# SSFocuser-B-TMC2208-O.net
KiCad netlist of a schematic drawn in Altium Designer
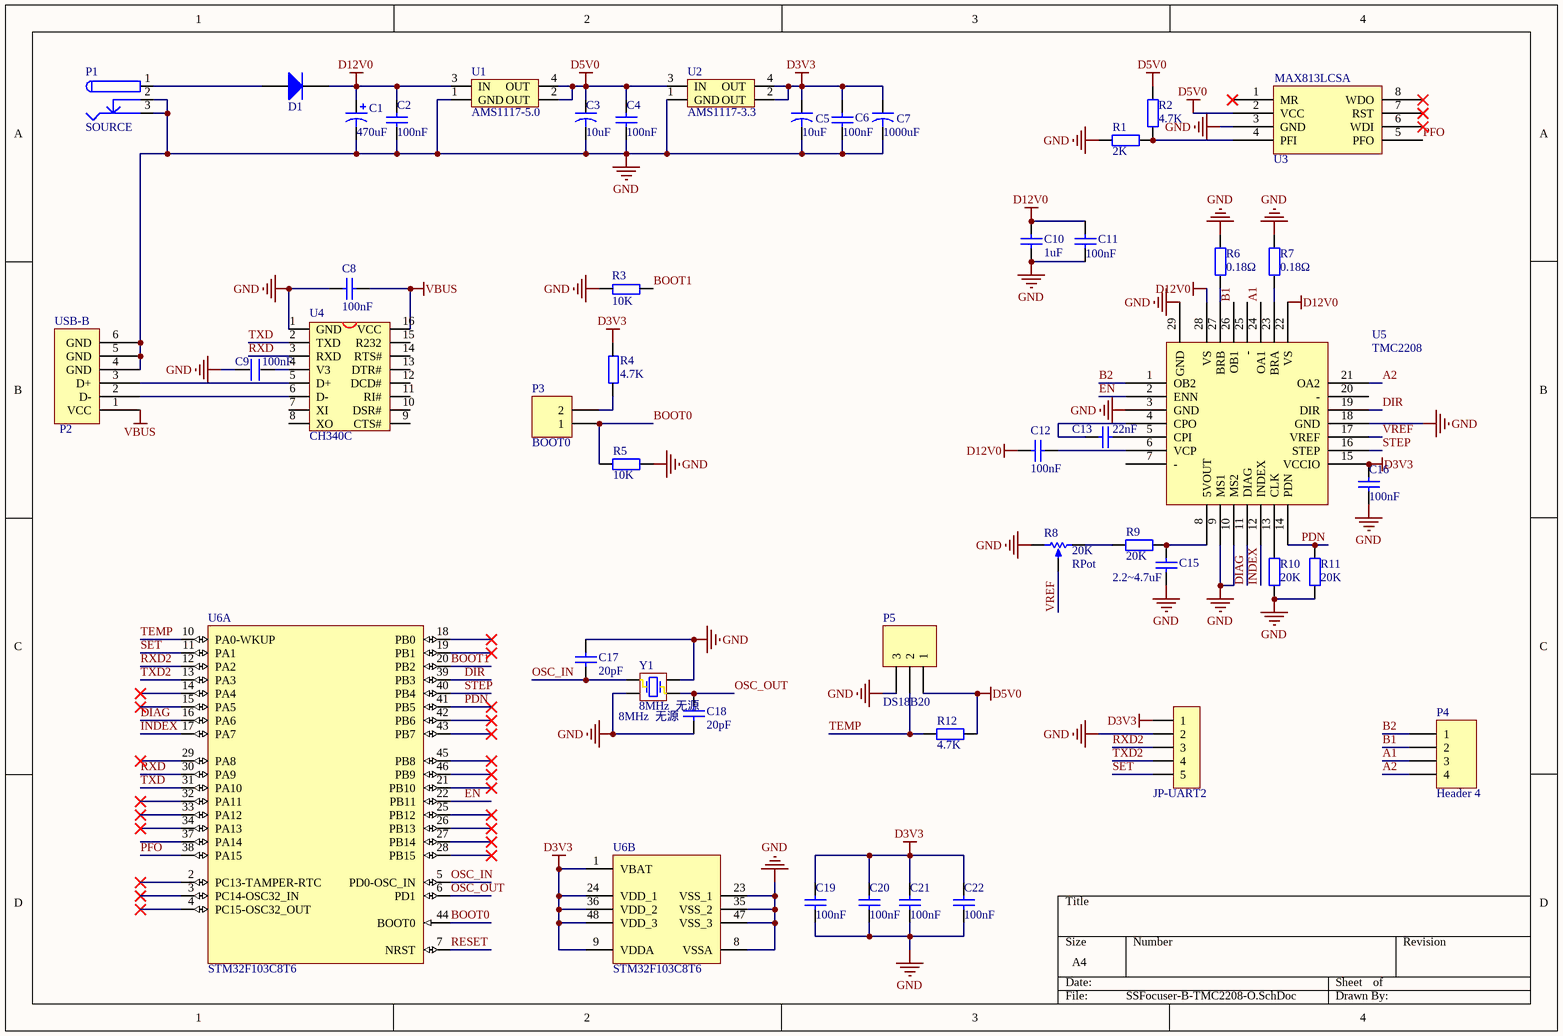
[diagram p0: SSFocuser-B-TMC2208-O.SchDoc]

(export (version "E")
  (design (tool "Eeschema 10.0.6"))
  (components
    (comp (ref "C1")
      (value "470uF")
      (footprint "16V/470U(CD10X10D5)")
      (description "470UF      16V      CD10X10D5")
      (libsource (lib "平台原理图symbol图库V1.0") (part "C470UF016S"))
    )
    (comp (ref "C2")
      (value "100nF")
      (footprint "0603C")
      (description "Capacitor")
      (fields (field (name "PUBLISHER") "Altium Limited"))
      (libsource (lib "Crazy_PCB") (part "Cap"))
    )
    (comp (ref "C3")
      (value "10uF")
      (footprint "3216")
      (fields (field (name "VAULE") "10uF"))
      (libsource (lib "Crazy_PCB") (part "CAP2"))
    )
    (comp (ref "C4")
      (value "100nF")
      (footprint "0603C")
      (description "Capacitor")
      (fields (field (name "PUBLISHER") "Altium Limited"))
      (libsource (lib "Crazy_PCB") (part "Cap"))
    )
    (comp (ref "C5")
      (value "10uF")
      (footprint "3216")
      (fields (field (name "VAULE") "10uF"))
      (libsource (lib "Crazy_PCB") (part "CAP2"))
    )
    (comp (ref "C6")
      (value "100nF")
      (footprint "0603C")
      (description "Capacitor")
      (fields (field (name "PUBLISHER") "Altium Limited"))
      (libsource (lib "Crazy_PCB") (part "Cap"))
    )
    (comp (ref "C7")
      (value "1000uF")
      (footprint "16V/470U(CD10X10D5)")
      (fields (field (name "VAULE") "1000uF"))
      (libsource (lib "Crazy_PCB") (part "CAP2"))
    )
    (comp (ref "C8")
      (value "100nF")
      (footprint "0603C")
      (description "Capacitor")
      (fields (field (name "PUBLISHER") "Altium Limited"))
      (libsource (lib "Crazy_PCB") (part "Cap"))
    )
    (comp (ref "C9")
      (value "100nF")
      (footprint "0603C")
      (libsource (lib "WarShip V3 STM32103封装库") (part "C"))
    )
    (comp (ref "C10")
      (value "1uF")
      (footprint "1206C")
      (description "Capacitor")
      (fields (field (name "PUBLISHER") "Altium Limited"))
      (libsource (lib "Crazy_PCB") (part "Cap"))
    )
    (comp (ref "C11")
      (value "100nF")
      (footprint "0603C")
      (description "Capacitor")
      (fields (field (name "PUBLISHER") "Altium Limited"))
      (libsource (lib "Crazy_PCB") (part "Cap"))
    )
    (comp (ref "C12")
      (value "100nF")
      (footprint "0603C")
      (description "Capacitor")
      (fields (field (name "PUBLISHER") "Altium Limited"))
      (libsource (lib "Crazy_PCB") (part "Cap"))
    )
    (comp (ref "C13")
      (value "22nF")
      (footprint "0603C")
      (description "Capacitor")
      (fields (field (name "PUBLISHER") "Altium Limited"))
      (libsource (lib "Crazy_PCB") (part "Cap"))
    )
    (comp (ref "C15")
      (value "2.2~4.7uF")
      (footprint "0603C")
      (description "Capacitor")
      (fields (field (name "PUBLISHER") "Altium Limited"))
      (libsource (lib "Crazy_PCB") (part "Cap"))
    )
    (comp (ref "C16")
      (value "100nF")
      (footprint "0603C")
      (description "Capacitor")
      (fields (field (name "PUBLISHER") "Altium Limited"))
      (libsource (lib "Crazy_PCB") (part "Cap"))
    )
    (comp (ref "C17")
      (value "20pF")
      (footprint "0603C")
      (description "Capacitor")
      (fields (field (name "PUBLISHER") "Altium Limited"))
      (libsource (lib "JL_SCH") (part "Cap"))
    )
    (comp (ref "C18")
      (value "20pF")
      (footprint "0603C")
      (description "Capacitor")
      (fields (field (name "PUBLISHER") "Altium Limited"))
      (libsource (lib "JL_SCH") (part "Cap"))
    )
    (comp (ref "C19")
      (value "100nF")
      (footprint "0603C")
      (description "Capacitor")
      (fields (field (name "PUBLISHER") "Altium Limited"))
      (libsource (lib "Crazy_PCB") (part "Cap"))
    )
    (comp (ref "C20")
      (value "100nF")
      (footprint "0603C")
      (description "Capacitor")
      (fields (field (name "PUBLISHER") "Altium Limited"))
      (libsource (lib "Crazy_PCB") (part "Cap"))
    )
    (comp (ref "C21")
      (value "100nF")
      (footprint "0603C")
      (description "Capacitor")
      (fields (field (name "PUBLISHER") "Altium Limited"))
      (libsource (lib "Crazy_PCB") (part "Cap"))
    )
    (comp (ref "C22")
      (value "100nF")
      (footprint "0603C")
      (description "Capacitor")
      (fields (field (name "PUBLISHER") "Altium Limited"))
      (libsource (lib "Crazy_PCB") (part "Cap"))
    )
    (comp (ref "D1")
      (value "M7")
      (footprint "DO-214AC")
      (description "High Conductance Fast Diode")
      (fields (field (name "PUBLISHER") "Altium Limited"))
      (libsource (lib "Crazy_PCB") (part "Diode"))
    )
    (comp (ref "JP-UART2")
      (value "HDR-1X5")
      (footprint "HDR2.54-LI-5P")
      (description "5P接插件")
      (fields (field (name "版权归属") "源创客"))
      (libsource (lib "4.5   - 接插件-脚距2.54") (part "Header 5"))
    )
    (comp (ref "P1")
      (value "SOURCE")
      (footprint "DC005")
      (fields (field (name "PUBLISHER") "Altium Limited"))
      (libsource (lib "Crazy_PCB") (part "SOURCE"))
    )
    (comp (ref "P2") (value "USB-B") (footprint "USB-B") (libsource (lib "DX") (part "USB-B")))
    (comp (ref "P3")
      (value "BOOT0")
      (footprint "HDR1X2")
      (description "Header, 2-Pin")
      (fields (field (name "PUBLISHER") "Altium Limited"))
      (libsource (lib "Miscellaneous Connectors") (part "MHDR1X2"))
    )
    (comp (ref "P4")
      (value "Header 4")
      (footprint "XH_4_V")
      (description "Header, 4-Pin")
      (fields (field (name "PUBLISHER") "Altium Limited"))
      (libsource (lib "Miscellaneous Connectors") (part "Header 4"))
    )
    (comp (ref "P5")
      (value "DS18B20")
      (footprint "TO-92B")
      (description "Header, 3-Pin")
      (fields (field (name "PUBLISHER") "Altium Limited"))
      (libsource (lib "Miscellaneous Connectors") (part "Header 3"))
    )
    (comp (ref "R1")
      (value "2K")
      (footprint "0603R")
      (description "Resistor")
      (fields (field (name "PUBLISHER") "Altium Limited"))
      (libsource (lib "") (part "RES_1"))
    )
    (comp (ref "R2")
      (value "4.7K")
      (footprint "0603R")
      (description "Resistor")
      (fields (field (name "PUBLISHER") "Altium Limited"))
      (libsource (lib "Crazy_PCB") (part "RES"))
    )
    (comp (ref "R3") (value "10K") (footprint "0603R") (libsource (lib "WarShip V3 STM32103封装库") (part "R")))
    (comp (ref "R4") (value "4.7K") (footprint "0603R") (libsource (lib "WarShip V3 STM32103封装库") (part "R")))
    (comp (ref "R5")
      (value "10K")
      (footprint "0603R")
      (description "Resistor")
      (fields (field (name "PUBLISHER") "Altium Limited"))
      (libsource (lib "") (part "RES_3"))
    )
    (comp (ref "R6")
      (value "0.18Ω")
      (footprint "1206R")
      (description "Resistor")
      (fields (field (name "PUBLISHER") "Altium Limited"))
      (libsource (lib "") (part "RES_2"))
    )
    (comp (ref "R7")
      (value "0.18Ω")
      (footprint "1206R")
      (description "Resistor")
      (fields (field (name "PUBLISHER") "Altium Limited"))
      (libsource (lib "") (part "RES_2"))
    )
    (comp (ref "R8")
      (value "RPot")
      (footprint "VR_SMD")
      (description "Potentiometer")
      (fields (field (name "ALTIUM_VALUE") "20K") (field (name "PUBLISHER") "Altium Limited"))
      (libsource (lib "Miscellaneous Devices") (part "RPot"))
    )
    (comp (ref "R9")
      (value "20K")
      (footprint "0603R")
      (description "Resistor")
      (fields (field (name "PUBLISHER") "Altium Limited"))
      (libsource (lib "") (part "RES_1"))
    )
    (comp (ref "R10")
      (value "20K")
      (footprint "0603R")
      (description "Resistor")
      (fields (field (name "PUBLISHER") "Altium Limited"))
      (libsource (lib "Crazy_PCB") (part "RES"))
    )
    (comp (ref "R11")
      (value "20K")
      (footprint "0603R")
      (description "Resistor")
      (fields (field (name "PUBLISHER") "Altium Limited"))
      (libsource (lib "Crazy_PCB") (part "RES"))
    )
    (comp (ref "R12")
      (value "4.7K")
      (footprint "0603R")
      (description "Resistor")
      (fields (field (name "PUBLISHER") "Altium Limited"))
      (libsource (lib "") (part "RES_3"))
    )
    (comp (ref "U1")
      (value "AMS1117-5.0")
      (footprint "SOT223")
      (libsource (lib "MiniSTM32 V3.0封装库") (part "AMS1117"))
    )
    (comp (ref "U2")
      (value "AMS1117-3.3")
      (footprint "SOT223")
      (libsource (lib "MiniSTM32 V3.0封装库") (part "AMS1117"))
    )
    (comp (ref "U3") (value "MAX813LCSA") (footprint "SOP-8") (libsource (lib "DX") (part "MAX813L")))
    (comp (ref "U4")
      (value "CH340C")
      (footprint "SO-16")
      (description "USB2UART")
      (libsource (lib "WarShip V3 STM32103封装库") (part "CH340G"))
    )
    (comp (ref "U5") (value "TMC2208") (footprint "QFN28") (libsource (lib "SS") (part "TMC2208")))
    (comp (ref "U6")
      (value "STM32F103C8T6")
      (footprint "LQFP48_N")
      (libsource (lib "STMicroelectronics STM32 F1") (part "STM32F103C8T6"))
    )
    (comp (ref "Y1")
      (value "8MHz  无源")
      (footprint "X3225")
      (description "Crystal Oscillator")
      (fields (field (name "ALTIUM_VALUE") "8MHz  无源") (field (name "PUBLISHER") "Altium Limited"))
      (libsource (lib "JL_SCH") (part "XTAL_1"))
    )
  )
  (nets
    (net (code "1") (name "/A1") (class "Default")
      (node (ref "P4") (pin "3") (pinfunction "3_3") (pintype "passive"))
      (node (ref "U5") (pin "24") (pinfunction "OA1_24") (pintype "passive"))
    )
    (net (code "2") (name "/A2") (class "Default")
      (node (ref "P4") (pin "4") (pinfunction "4_4") (pintype "passive"))
      (node (ref "U5") (pin "21") (pinfunction "OA2_21") (pintype "passive"))
    )
    (net (code "3") (name "/B1") (class "Default")
      (node (ref "P4") (pin "2") (pinfunction "2_2") (pintype "passive"))
      (node (ref "U5") (pin "26") (pinfunction "OB1_26") (pintype "passive"))
    )
    (net (code "4") (name "/B2") (class "Default")
      (node (ref "P4") (pin "1") (pinfunction "1_1") (pintype "passive"))
      (node (ref "U5") (pin "1") (pinfunction "OB2_1") (pintype "passive"))
    )
    (net (code "5") (name "/BOOT0") (class "Default")
      (node (ref "P3") (pin "1") (pinfunction "1_1") (pintype "passive"))
      (node (ref "R5") (pin "1") (pinfunction "1_1") (pintype "passive"))
      (node (ref "U6") (pin "44") (pinfunction "BOOT0_44") (pintype "input"))
    )
    (net (code "6") (name "/BOOT1") (class "Default")
      (node (ref "R3") (pin "2") (pintype "passive"))
      (node (ref "U6") (pin "20") (pinfunction "PB2_20") (pintype "bidirectional"))
    )
    (net (code "7") (name "/DIAG") (class "Default")
      (node (ref "U5") (pin "11") (pinfunction "DIAG_11") (pintype "passive"))
      (node (ref "U6") (pin "16") (pinfunction "PA6_16") (pintype "bidirectional"))
    )
    (net (code "8") (name "/DIR") (class "Default")
      (node (ref "U5") (pin "19") (pinfunction "DIR_19") (pintype "passive"))
      (node (ref "U6") (pin "39") (pinfunction "PB3_39") (pintype "bidirectional"))
    )
    (net (code "9") (name "/EN") (class "Default")
      (node (ref "U5") (pin "2") (pinfunction "ENN_2") (pintype "passive"))
      (node (ref "U6") (pin "22") (pinfunction "PB11_22") (pintype "bidirectional"))
    )
    (net (code "10") (name "/INDEX") (class "Default")
      (node (ref "U5") (pin "12") (pinfunction "INDEX_12") (pintype "passive"))
      (node (ref "U6") (pin "17") (pinfunction "PA7_17") (pintype "bidirectional"))
    )
    (net (code "11") (name "/OSC_IN") (class "Default")
      (node (ref "C17") (pin "1") (pinfunction "1_1") (pintype "passive"))
      (node (ref "U6") (pin "5") (pinfunction "PD0-OSC_IN_5") (pintype "bidirectional"))
      (node (ref "Y1") (pin "1") (pinfunction "OSC1_1") (pintype "passive"))
    )
    (net (code "12") (name "/OSC_OUT") (class "Default")
      (node (ref "C18") (pin "1") (pinfunction "1_1") (pintype "passive"))
      (node (ref "U6") (pin "6") (pinfunction "PD1_6") (pintype "bidirectional"))
      (node (ref "Y1") (pin "3") (pinfunction "OSC2_3") (pintype "passive"))
    )
    (net (code "13") (name "/PDN") (class "Default")
      (node (ref "R11") (pin "2") (pinfunction "2_2") (pintype "passive"))
      (node (ref "U5") (pin "14") (pinfunction "PDN_14") (pintype "passive"))
      (node (ref "U6") (pin "41") (pinfunction "PB5_41") (pintype "bidirectional"))
    )
    (net (code "14") (name "/PFO") (class "Default")
      (node (ref "U3") (pin "5") (pinfunction "PFO_5") (pintype "passive"))
      (node (ref "U6") (pin "38") (pinfunction "PA15_38") (pintype "bidirectional"))
    )
    (net (code "15") (name "/RESET") (class "Default")
      (node (ref "U6") (pin "7") (pinfunction "NRST_7") (pintype "bidirectional"))
    )
    (net (code "16") (name "/RXD") (class "Default")
      (node (ref "U4") (pin "3") (pinfunction "RXD_3") (pintype "passive"))
      (node (ref "U6") (pin "30") (pinfunction "PA9_30") (pintype "bidirectional"))
    )
    (net (code "17") (name "/RXD2") (class "Default")
      (node (ref "JP-UART2") (pin "3") (pinfunction "3_3") (pintype "passive"))
      (node (ref "U6") (pin "12") (pinfunction "PA2_12") (pintype "bidirectional"))
    )
    (net (code "18") (name "/SET") (class "Default")
      (node (ref "JP-UART2") (pin "5") (pinfunction "5_5") (pintype "passive"))
      (node (ref "U6") (pin "11") (pinfunction "PA1_11") (pintype "bidirectional"))
    )
    (net (code "19") (name "/STEP") (class "Default")
      (node (ref "U5") (pin "16") (pinfunction "STEP_16") (pintype "passive"))
      (node (ref "U6") (pin "40") (pinfunction "PB4_40") (pintype "bidirectional"))
    )
    (net (code "20") (name "/TEMP") (class "Default")
      (node (ref "P5") (pin "2") (pinfunction "2_2") (pintype "passive"))
      (node (ref "R12") (pin "1") (pinfunction "1_1") (pintype "passive"))
      (node (ref "U6") (pin "10") (pinfunction "PA0-WKUP_10") (pintype "bidirectional"))
    )
    (net (code "21") (name "/TXD") (class "Default")
      (node (ref "U4") (pin "2") (pinfunction "TXD_2") (pintype "passive"))
      (node (ref "U6") (pin "31") (pinfunction "PA10_31") (pintype "bidirectional"))
    )
    (net (code "22") (name "/TXD2") (class "Default")
      (node (ref "JP-UART2") (pin "4") (pinfunction "4_4") (pintype "passive"))
      (node (ref "U6") (pin "13") (pinfunction "PA3_13") (pintype "bidirectional"))
    )
    (net (code "23") (name "/VREF") (class "Default")
      (node (ref "R8") (pin "3") (pinfunction "TAP_3") (pintype "passive"))
      (node (ref "U5") (pin "17") (pinfunction "VREF_17") (pintype "passive"))
    )
    (net (code "24") (name "D3V3") (class "Default")
      (node (ref "C16") (pin "2") (pinfunction "2_2") (pintype "passive"))
      (node (ref "C19") (pin "2") (pinfunction "2_2") (pintype "passive"))
      (node (ref "C20") (pin "2") (pinfunction "2_2") (pintype "passive"))
      (node (ref "C21") (pin "2") (pinfunction "2_2") (pintype "passive"))
      (node (ref "C22") (pin "2") (pinfunction "2_2") (pintype "passive"))
      (node (ref "C5") (pin "1") (pinfunction "1_1") (pintype "passive"))
      (node (ref "C6") (pin "2") (pinfunction "2_2") (pintype "passive"))
      (node (ref "C7") (pin "1") (pinfunction "1_1") (pintype "passive"))
      (node (ref "JP-UART2") (pin "1") (pinfunction "1_1") (pintype "passive"))
      (node (ref "R4") (pin "2") (pintype "passive"))
      (node (ref "U2") (pin "2") (pinfunction "OUT_2") (pintype "passive"))
      (node (ref "U2") (pin "4") (pinfunction "OUT_4") (pintype "passive"))
      (node (ref "U5") (pin "15") (pinfunction "VCCIO_15") (pintype "passive"))
      (node (ref "U6") (pin "1") (pinfunction "VBAT_1") (pintype "power_in"))
      (node (ref "U6") (pin "24") (pinfunction "VDD_1_24") (pintype "power_in"))
      (node (ref "U6") (pin "36") (pinfunction "VDD_2_36") (pintype "power_in"))
      (node (ref "U6") (pin "48") (pinfunction "VDD_3_48") (pintype "power_in"))
      (node (ref "U6") (pin "9") (pinfunction "VDDA_9") (pintype "power_in"))
    )
    (net (code "25") (name "D5V0") (class "Default")
      (node (ref "C3") (pin "1") (pinfunction "1_1") (pintype "passive"))
      (node (ref "C4") (pin "2") (pinfunction "2_2") (pintype "passive"))
      (node (ref "P5") (pin "1") (pinfunction "1_1") (pintype "passive"))
      (node (ref "R12") (pin "2") (pinfunction "2_2") (pintype "passive"))
      (node (ref "R2") (pin "2") (pinfunction "2_2") (pintype "passive"))
      (node (ref "U1") (pin "2") (pinfunction "OUT_2") (pintype "passive"))
      (node (ref "U1") (pin "4") (pinfunction "OUT_4") (pintype "passive"))
      (node (ref "U2") (pin "3") (pinfunction "IN_3") (pintype "passive"))
      (node (ref "U3") (pin "2") (pinfunction "VCC_2") (pintype "passive"))
    )
    (net (code "26") (name "D12V0") (class "Default")
      (node (ref "C1") (pin "1") (pinfunction "1_1") (pintype "passive"))
      (node (ref "C10") (pin "1") (pinfunction "1_1") (pintype "passive"))
      (node (ref "C11") (pin "2") (pinfunction "2_2") (pintype "passive"))
      (node (ref "C12") (pin "2") (pinfunction "2_2") (pintype "passive"))
      (node (ref "C2") (pin "2") (pinfunction "2_2") (pintype "passive"))
      (node (ref "D1") (pin "2") (pinfunction "K_2") (pintype "passive"))
      (node (ref "U1") (pin "3") (pinfunction "IN_3") (pintype "passive"))
      (node (ref "U5") (pin "22") (pinfunction "VS_22") (pintype "passive"))
      (node (ref "U5") (pin "28") (pinfunction "VS_28") (pintype "passive"))
    )
    (net (code "27") (name "GND") (class "Default")
      (node (ref "C1") (pin "2") (pinfunction "2_2") (pintype "passive"))
      (node (ref "C10") (pin "2") (pinfunction "2_2") (pintype "passive"))
      (node (ref "C11") (pin "1") (pinfunction "1_1") (pintype "passive"))
      (node (ref "C15") (pin "1") (pinfunction "1_1") (pintype "passive"))
      (node (ref "C16") (pin "1") (pinfunction "1_1") (pintype "passive"))
      (node (ref "C17") (pin "2") (pinfunction "2_2") (pintype "passive"))
      (node (ref "C18") (pin "2") (pinfunction "2_2") (pintype "passive"))
      (node (ref "C19") (pin "1") (pinfunction "1_1") (pintype "passive"))
      (node (ref "C2") (pin "1") (pinfunction "1_1") (pintype "passive"))
      (node (ref "C20") (pin "1") (pinfunction "1_1") (pintype "passive"))
      (node (ref "C21") (pin "1") (pinfunction "1_1") (pintype "passive"))
      (node (ref "C22") (pin "1") (pinfunction "1_1") (pintype "passive"))
      (node (ref "C3") (pin "2") (pinfunction "2_2") (pintype "passive"))
      (node (ref "C4") (pin "1") (pinfunction "1_1") (pintype "passive"))
      (node (ref "C5") (pin "2") (pinfunction "2_2") (pintype "passive"))
      (node (ref "C6") (pin "1") (pinfunction "1_1") (pintype "passive"))
      (node (ref "C7") (pin "2") (pinfunction "2_2") (pintype "passive"))
      (node (ref "C8") (pin "1") (pinfunction "1_1") (pintype "passive"))
      (node (ref "C9") (pin "1") (pintype "passive"))
      (node (ref "JP-UART2") (pin "2") (pinfunction "2_2") (pintype "passive"))
      (node (ref "P1") (pin "2") (pinfunction "2_2") (pintype "power_in"))
      (node (ref "P1") (pin "3") (pinfunction "3_3") (pintype "power_in"))
      (node (ref "P2") (pin "4") (pinfunction "GND_4") (pintype "passive"))
      (node (ref "P2") (pin "5") (pinfunction "GND_5") (pintype "passive"))
      (node (ref "P2") (pin "6") (pinfunction "GND_6") (pintype "passive"))
      (node (ref "P5") (pin "3") (pinfunction "3_3") (pintype "passive"))
      (node (ref "R1") (pin "2") (pinfunction "2_2") (pintype "passive"))
      (node (ref "R10") (pin "1") (pinfunction "1_1") (pintype "passive"))
      (node (ref "R11") (pin "1") (pinfunction "1_1") (pintype "passive"))
      (node (ref "R3") (pin "1") (pintype "passive"))
      (node (ref "R5") (pin "2") (pinfunction "2_2") (pintype "passive"))
      (node (ref "R6") (pin "1") (pinfunction "1_1") (pintype "passive"))
      (node (ref "R7") (pin "1") (pinfunction "1_1") (pintype "passive"))
      (node (ref "R8") (pin "1") (pinfunction "TOP_1") (pintype "passive"))
      (node (ref "U1") (pin "1") (pinfunction "GND_1") (pintype "passive"))
      (node (ref "U2") (pin "1") (pinfunction "GND_1") (pintype "passive"))
      (node (ref "U3") (pin "3") (pinfunction "GND_3") (pintype "passive"))
      (node (ref "U4") (pin "1") (pinfunction "GND_1") (pintype "passive"))
      (node (ref "U5") (pin "10") (pinfunction "MS2_10") (pintype "passive"))
      (node (ref "U5") (pin "18") (pinfunction "GND_18") (pintype "passive"))
      (node (ref "U5") (pin "29") (pinfunction "GND_29") (pintype "passive"))
      (node (ref "U5") (pin "3") (pinfunction "GND_3") (pintype "passive"))
      (node (ref "U5") (pin "9") (pinfunction "MS1_9") (pintype "passive"))
      (node (ref "U6") (pin "23") (pinfunction "VSS_1_23") (pintype "power_in"))
      (node (ref "U6") (pin "35") (pinfunction "VSS_2_35") (pintype "power_in"))
      (node (ref "U6") (pin "47") (pinfunction "VSS_3_47") (pintype "power_in"))
      (node (ref "U6") (pin "8") (pinfunction "VSSA_8") (pintype "power_in"))
      (node (ref "Y1") (pin "2") (pinfunction "NA_2") (pintype "passive"))
      (node (ref "Y1") (pin "4") (pinfunction "NA_4") (pintype "passive"))
    )
    (net (code "28") (name "Net-(D1-A)") (class "Default")
      (node (ref "D1") (pin "1") (pinfunction "A_1") (pintype "passive"))
      (node (ref "P1") (pin "1") (pinfunction "1_1") (pintype "power_in"))
    )
    (net (code "29") (name "Net-(P2-D+)") (class "Default")
      (node (ref "P2") (pin "3") (pinfunction "D+_3") (pintype "passive"))
      (node (ref "U4") (pin "5") (pinfunction "D+_5") (pintype "passive"))
    )
    (net (code "30") (name "Net-(P2-D-)") (class "Default")
      (node (ref "P2") (pin "2") (pinfunction "D-_2") (pintype "passive"))
      (node (ref "U4") (pin "6") (pinfunction "D-_6") (pintype "passive"))
    )
    (net (code "31") (name "Net-(P3-Pad2)") (class "Default")
      (node (ref "P3") (pin "2") (pinfunction "2_2") (pintype "passive"))
      (node (ref "R4") (pin "1") (pintype "passive"))
    )
    (net (code "32") (name "Net-(R8-BOT)") (class "Default")
      (node (ref "R8") (pin "2") (pinfunction "BOT_2") (pintype "passive"))
      (node (ref "R9") (pin "2") (pinfunction "2_2") (pintype "passive"))
    )
    (net (code "33") (name "Net-(U3-PFI)") (class "Default")
      (node (ref "R1") (pin "1") (pinfunction "1_1") (pintype "passive"))
      (node (ref "R2") (pin "1") (pinfunction "1_1") (pintype "passive"))
      (node (ref "U3") (pin "4") (pinfunction "PFI_4") (pintype "passive"))
    )
    (net (code "34") (name "Net-(U4-V3)") (class "Default")
      (node (ref "C9") (pin "2") (pintype "passive"))
      (node (ref "U4") (pin "4") (pinfunction "V3_4") (pintype "passive"))
    )
    (net (code "35") (name "Net-(U5-5VOUT)") (class "Default")
      (node (ref "C15") (pin "2") (pinfunction "2_2") (pintype "passive"))
      (node (ref "R9") (pin "1") (pinfunction "1_1") (pintype "passive"))
      (node (ref "U5") (pin "8") (pinfunction "5VOUT_8") (pintype "passive"))
    )
    (net (code "36") (name "Net-(U5-BRA)") (class "Default")
      (node (ref "R7") (pin "2") (pinfunction "2_2") (pintype "passive"))
      (node (ref "U5") (pin "23") (pinfunction "BRA_23") (pintype "passive"))
    )
    (net (code "37") (name "Net-(U5-BRB)") (class "Default")
      (node (ref "R6") (pin "2") (pinfunction "2_2") (pintype "passive"))
      (node (ref "U5") (pin "27") (pinfunction "BRB_27") (pintype "passive"))
    )
    (net (code "38") (name "Net-(U5-CLK)") (class "Default")
      (node (ref "R10") (pin "2") (pinfunction "2_2") (pintype "passive"))
      (node (ref "U5") (pin "13") (pinfunction "CLK_13") (pintype "passive"))
    )
    (net (code "39") (name "Net-(U5-CPI)") (class "Default")
      (node (ref "C13") (pin "1") (pinfunction "1_1") (pintype "passive"))
      (node (ref "U5") (pin "5") (pinfunction "CPI_5") (pintype "passive"))
    )
    (net (code "40") (name "Net-(U5-CPO)") (class "Default")
      (node (ref "C13") (pin "2") (pinfunction "2_2") (pintype "passive"))
      (node (ref "U5") (pin "4") (pinfunction "CPO_4") (pintype "passive"))
    )
    (net (code "41") (name "Net-(U5-VCP)") (class "Default")
      (node (ref "C12") (pin "1") (pinfunction "1_1") (pintype "passive"))
      (node (ref "U5") (pin "6") (pinfunction "VCP_6") (pintype "passive"))
    )
    (net (code "42") (name "VBUS") (class "Default")
      (node (ref "C8") (pin "2") (pinfunction "2_2") (pintype "passive"))
      (node (ref "P2") (pin "1") (pinfunction "VCC_1") (pintype "passive"))
      (node (ref "U4") (pin "16") (pinfunction "VCC_16") (pintype "passive"))
    )
    (net (code "43") (name "unconnected-(U3-MR-Pad1)") (class "Default")
      (node (ref "U3") (pin "1") (pinfunction "MR_1") (pintype "passive+no_connect"))
    )
    (net (code "44") (name "unconnected-(U3-RST-Pad7)") (class "Default")
      (node (ref "U3") (pin "7") (pinfunction "RST_7") (pintype "passive+no_connect"))
    )
    (net (code "45") (name "unconnected-(U3-WDI-Pad6)") (class "Default")
      (node (ref "U3") (pin "6") (pinfunction "WDI_6") (pintype "passive+no_connect"))
    )
    (net (code "46") (name "unconnected-(U3-WDO-Pad8)") (class "Default")
      (node (ref "U3") (pin "8") (pinfunction "WDO_8") (pintype "passive+no_connect"))
    )
    (net (code "47") (name "unconnected-(U4-CTS#-Pad9)") (class "Default")
      (node (ref "U4") (pin "9") (pinfunction "CTS#_9") (pintype "passive"))
    )
    (net (code "48") (name "unconnected-(U4-DCD#-Pad12)") (class "Default")
      (node (ref "U4") (pin "12") (pinfunction "DCD#_12") (pintype "passive"))
    )
    (net (code "49") (name "unconnected-(U4-DSR#-Pad10)") (class "Default")
      (node (ref "U4") (pin "10") (pinfunction "DSR#_10") (pintype "passive"))
    )
    (net (code "50") (name "unconnected-(U4-DTR#-Pad13)") (class "Default")
      (node (ref "U4") (pin "13") (pinfunction "DTR#_13") (pintype "passive"))
    )
    (net (code "51") (name "unconnected-(U4-R232-Pad15)") (class "Default")
      (node (ref "U4") (pin "15") (pinfunction "R232_15") (pintype "passive"))
    )
    (net (code "52") (name "unconnected-(U4-RI#-Pad11)") (class "Default")
      (node (ref "U4") (pin "11") (pinfunction "RI#_11") (pintype "passive"))
    )
    (net (code "53") (name "unconnected-(U4-RTS#-Pad14)") (class "Default")
      (node (ref "U4") (pin "14") (pinfunction "RTS#_14") (pintype "passive"))
    )
    (net (code "54") (name "unconnected-(U4-XI-Pad7)") (class "Default")
      (node (ref "U4") (pin "7") (pinfunction "XI_7") (pintype "passive"))
    )
    (net (code "55") (name "unconnected-(U4-XO-Pad8)") (class "Default")
      (node (ref "U4") (pin "8") (pinfunction "XO_8") (pintype "passive"))
    )
    (net (code "56") (name "unconnected-(U5---Pad7)") (class "Default")
      (node (ref "U5") (pin "7") (pinfunction "-_7") (pintype "passive"))
    )
    (net (code "57") (name "unconnected-(U5---Pad20)") (class "Default")
      (node (ref "U5") (pin "20") (pinfunction "-_20") (pintype "passive"))
    )
    (net (code "58") (name "unconnected-(U5---Pad25)") (class "Default")
      (node (ref "U5") (pin "25") (pinfunction "-_25") (pintype "passive"))
    )
    (net (code "59") (name "unconnected-(U6A-PA4-Pad14)") (class "Default")
      (node (ref "U6") (pin "14") (pinfunction "PA4_14") (pintype "bidirectional+no_connect"))
    )
    (net (code "60") (name "unconnected-(U6A-PA5-Pad15)") (class "Default")
      (node (ref "U6") (pin "15") (pinfunction "PA5_15") (pintype "bidirectional+no_connect"))
    )
    (net (code "61") (name "unconnected-(U6A-PA8-Pad29)") (class "Default")
      (node (ref "U6") (pin "29") (pinfunction "PA8_29") (pintype "bidirectional+no_connect"))
    )
    (net (code "62") (name "unconnected-(U6A-PA11-Pad32)") (class "Default")
      (node (ref "U6") (pin "32") (pinfunction "PA11_32") (pintype "bidirectional+no_connect"))
    )
    (net (code "63") (name "unconnected-(U6A-PA12-Pad33)") (class "Default")
      (node (ref "U6") (pin "33") (pinfunction "PA12_33") (pintype "bidirectional+no_connect"))
    )
    (net (code "64") (name "unconnected-(U6A-PA13-Pad34)") (class "Default")
      (node (ref "U6") (pin "34") (pinfunction "PA13_34") (pintype "bidirectional+no_connect"))
    )
    (net (code "65") (name "unconnected-(U6A-PA14-Pad37)") (class "Default")
      (node (ref "U6") (pin "37") (pinfunction "PA14_37") (pintype "bidirectional"))
    )
    (net (code "66") (name "unconnected-(U6A-PB0-Pad18)") (class "Default")
      (node (ref "U6") (pin "18") (pinfunction "PB0_18") (pintype "bidirectional+no_connect"))
    )
    (net (code "67") (name "unconnected-(U6A-PB1-Pad19)") (class "Default")
      (node (ref "U6") (pin "19") (pinfunction "PB1_19") (pintype "bidirectional+no_connect"))
    )
    (net (code "68") (name "unconnected-(U6A-PB6-Pad42)") (class "Default")
      (node (ref "U6") (pin "42") (pinfunction "PB6_42") (pintype "bidirectional+no_connect"))
    )
    (net (code "69") (name "unconnected-(U6A-PB7-Pad43)") (class "Default")
      (node (ref "U6") (pin "43") (pinfunction "PB7_43") (pintype "bidirectional+no_connect"))
    )
    (net (code "70") (name "unconnected-(U6A-PB8-Pad45)") (class "Default")
      (node (ref "U6") (pin "45") (pinfunction "PB8_45") (pintype "bidirectional+no_connect"))
    )
    (net (code "71") (name "unconnected-(U6A-PB9-Pad46)") (class "Default")
      (node (ref "U6") (pin "46") (pinfunction "PB9_46") (pintype "bidirectional+no_connect"))
    )
    (net (code "72") (name "unconnected-(U6A-PB10-Pad21)") (class "Default")
      (node (ref "U6") (pin "21") (pinfunction "PB10_21") (pintype "bidirectional+no_connect"))
    )
    (net (code "73") (name "unconnected-(U6A-PB12-Pad25)") (class "Default")
      (node (ref "U6") (pin "25") (pinfunction "PB12_25") (pintype "bidirectional+no_connect"))
    )
    (net (code "74") (name "unconnected-(U6A-PB13-Pad26)") (class "Default")
      (node (ref "U6") (pin "26") (pinfunction "PB13_26") (pintype "bidirectional+no_connect"))
    )
    (net (code "75") (name "unconnected-(U6A-PB14-Pad27)") (class "Default")
      (node (ref "U6") (pin "27") (pinfunction "PB14_27") (pintype "bidirectional+no_connect"))
    )
    (net (code "76") (name "unconnected-(U6A-PB15-Pad28)") (class "Default")
      (node (ref "U6") (pin "28") (pinfunction "PB15_28") (pintype "bidirectional+no_connect"))
    )
    (net (code "77") (name "unconnected-(U6A-PC13-TAMPER-RTC-Pad2)") (class "Default")
      (node (ref "U6") (pin "2") (pinfunction "PC13-TAMPER-RTC_2") (pintype "bidirectional+no_connect"))
    )
    (net (code "78") (name "unconnected-(U6A-PC14-OSC32_IN-Pad3)") (class "Default")
      (node (ref "U6") (pin "3") (pinfunction "PC14-OSC32_IN_3") (pintype "bidirectional+no_connect"))
    )
    (net (code "79") (name "unconnected-(U6A-PC15-OSC32_OUT-Pad4)") (class "Default")
      (node (ref "U6") (pin "4") (pinfunction "PC15-OSC32_OUT_4") (pintype "bidirectional+no_connect"))
    )
  )
)
